# FTDI.net
KiCad netlist of a schematic drawn in Altium Designer
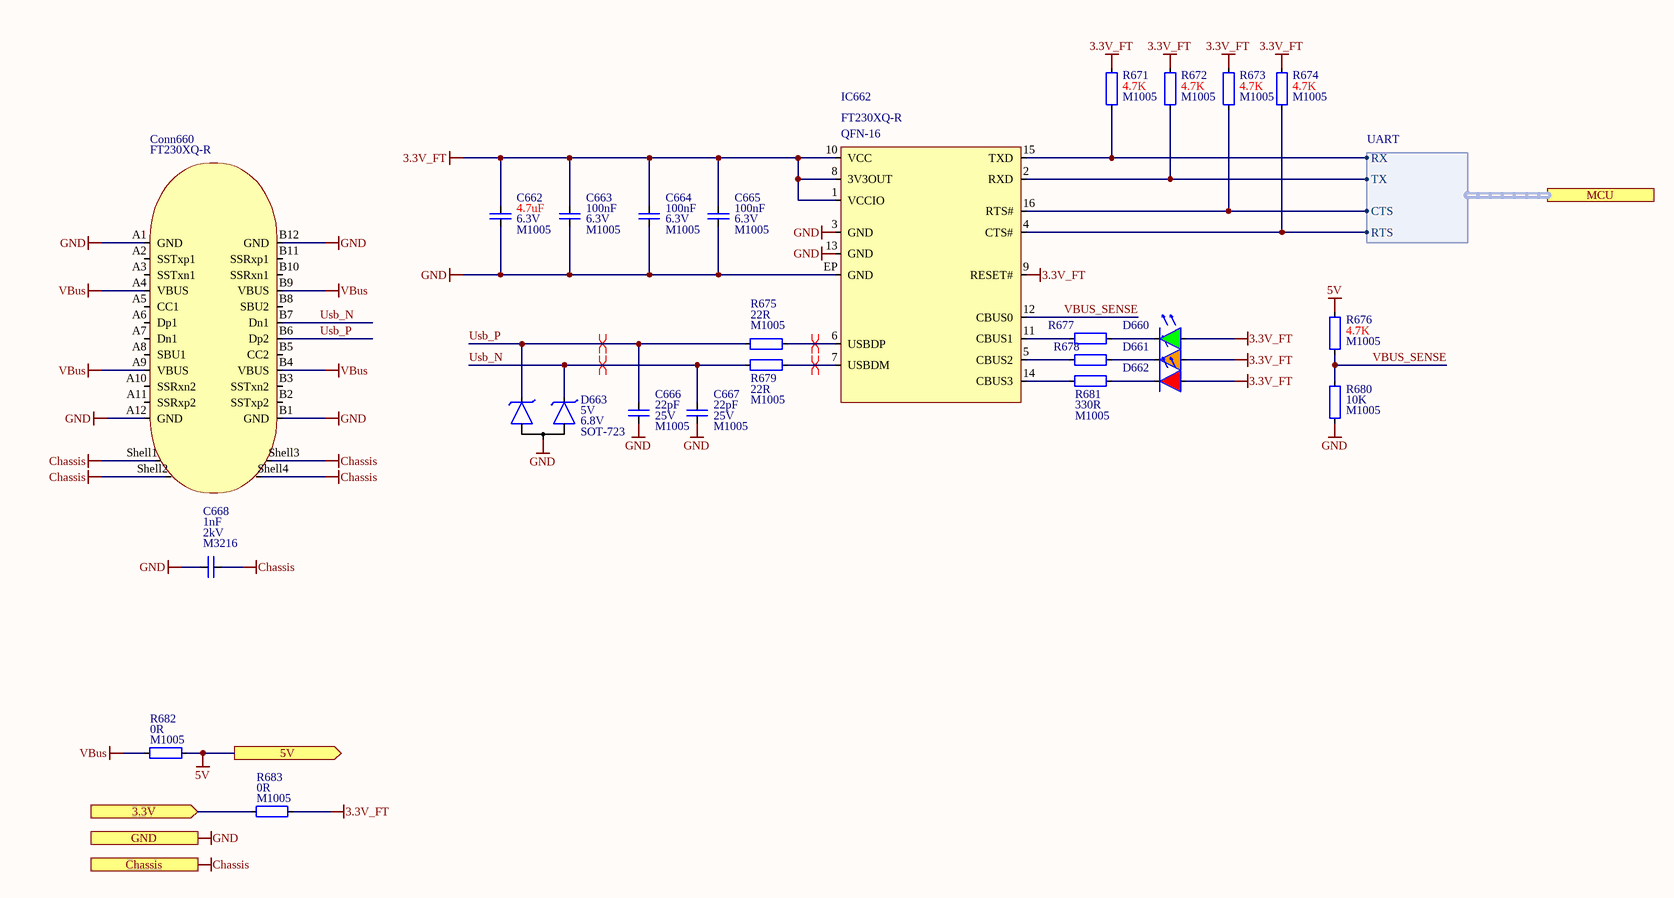
[diagram p0: FTDI.SchDoc]

(export (version "E")
  (design (tool "Eeschema 10.0.6"))
  (components
    (comp (ref "C662")
      (value "4.7uF")
      (footprint "Capacitor_Ceramic_M1005_I0402")
      (description "Cap, Cer, 100nF, 6.3V, M1005")
      (fields
        (field (name "VOLTAGE") "6.3V")
        (field (name "MANUFACTURER PART NUMBER") "04026D104KAT4A")
        (field (name "MANUFACTURER") "Kyocera")
        (field (name "PACKAGE") "M1005")
      )
      (libsource (lib "Capacitor") (part "Capacitor_Ceramic"))
    )
    (comp (ref "C663")
      (value "100nF")
      (footprint "Capacitor_Ceramic_M1005_I0402")
      (description "Cap, Cer, 100nF, 6.3V, M1005")
      (fields
        (field (name "VOLTAGE") "6.3V")
        (field (name "MANUFACTURER PART NUMBER") "04026D104KAT4A")
        (field (name "MANUFACTURER") "Kyocera")
        (field (name "PACKAGE") "M1005")
      )
      (libsource (lib "Capacitor") (part "Capacitor_Ceramic"))
    )
    (comp (ref "C664")
      (value "100nF")
      (footprint "Capacitor_Ceramic_M1005_I0402")
      (description "Cap, Cer, 100nF, 6.3V, M1005")
      (fields
        (field (name "VOLTAGE") "6.3V")
        (field (name "MANUFACTURER PART NUMBER") "04026D104KAT4A")
        (field (name "MANUFACTURER") "Kyocera")
        (field (name "PACKAGE") "M1005")
      )
      (libsource (lib "Capacitor") (part "Capacitor_Ceramic"))
    )
    (comp (ref "C665")
      (value "100nF")
      (footprint "Capacitor_Ceramic_M1005_I0402")
      (description "Cap, Cer, 100nF, 6.3V, M1005")
      (fields
        (field (name "VOLTAGE") "6.3V")
        (field (name "MANUFACTURER PART NUMBER") "04026D104KAT4A")
        (field (name "MANUFACTURER") "Kyocera")
        (field (name "PACKAGE") "M1005")
      )
      (libsource (lib "Capacitor") (part "Capacitor_Ceramic"))
    )
    (comp (ref "C666")
      (value "22pF")
      (footprint "Capacitor_Ceramic_M1005_I0402")
      (description "Cap, Cer, 22pF, 25V, M1005")
      (fields
        (field (name "VOLTAGE") "25V")
        (field (name "MANUFACTURER PART NUMBER") "0402N220J250CT")
        (field (name "MANUFACTURER") "Walsin")
        (field (name "PACKAGE") "M1005")
      )
      (libsource (lib "Capacitor") (part "Capacitor_Ceramic"))
    )
    (comp (ref "C667")
      (value "22pF")
      (footprint "Capacitor_Ceramic_M1005_I0402")
      (description "Cap, Cer, 22pF, 25V, M1005")
      (fields
        (field (name "VOLTAGE") "25V")
        (field (name "MANUFACTURER PART NUMBER") "0402N220J250CT")
        (field (name "MANUFACTURER") "Walsin")
        (field (name "PACKAGE") "M1005")
      )
      (libsource (lib "Capacitor") (part "Capacitor_Ceramic"))
    )
    (comp (ref "C668")
      (value "1nF")
      (footprint "Capacitor_Ceramic_M3216_I1206")
      (description "Cap, Cer, 1nF, 2kV, M3216")
      (fields
        (field (name "VOLTAGE") "2kV")
        (field (name "MANUFACTURER PART NUMBER") "CC1206MKX7RDBB102")
        (field (name "MANUFACTURER") "Yageo")
        (field (name "PACKAGE") "M3216")
      )
      (libsource (lib "Capacitor") (part "Capacitor_Ceramic"))
    )
    (comp (ref "Conn660")
      (value "GCT, USB4056")
      (footprint "GCT, USB4056")
      (description "IC,Interface,FTDI,QFN16")
      (fields (field (name "MANUFACTURER") "FTDI") (field (name "MANUFACTURER PART NUMBER") "FT230XQ-R"))
      (libsource (lib "Connector - USB") (part "GCT, USB4056"))
    )
    (comp (ref "D660")
      (value "Diode_Led")
      (footprint "Diode_Smd_M1608_I0603_Green-Yellow")
      (description "Diode, Led, Green-Yellow, 2.2V, 20mA, M1608")
      (fields (field (name "MANUFACTURER PART NUMBER") "SML-D12M1WT86") (field (name "MANUFACTURER") "Rohm"))
      (libsource (lib "Diode") (part "Diode_Led"))
    )
    (comp (ref "D661")
      (value "Diode_Led")
      (footprint "Diode_Smd_M1608_I0603_Orange1")
      (description "Diode, Led, Orange, 2.2V, 20mA, M1608")
      (fields (field (name "MANUFACTURER PART NUMBER") "SML-D12D1WT86") (field (name "MANUFACTURER") "Rohm"))
      (libsource (lib "Diode") (part "Diode_Led"))
    )
    (comp (ref "D662")
      (value "Diode_Led")
      (footprint "Diode_Smd_M1608_I0603_Red")
      (description "Diode, Led, Red, 2.2V, 20mA, M1608")
      (fields (field (name "MANUFACTURER PART NUMBER") "SML-D12U1WT86") (field (name "MANUFACTURER") "Rohm"))
      (libsource (lib "Diode") (part "Diode_Led"))
    )
    (comp (ref "D663")
      (value "Diode_Tvs_2P_Common_Anode")
      (footprint "Diode_SOT-723_2P_Common_Anode_Type_1")
      (description "Diode, TVS, 5V/6.8V, SOD-723")
      (fields
        (field (name "MANUFACTURER PART NUMBER") "DF3A6.8LFV,L3F")
        (field (name "MANUFACTURER") "Toshiba")
        (field (name "VOLTAGE, BREAK DOWN") "6.8V")
        (field (name "VOLTAGE, STAND OFF") "5V")
        (field (name "PACKAGE") "SOT-723")
      )
      (libsource (lib "Diode") (part "Diode_Tvs_2P_Common_Anode"))
    )
    (comp (ref "IC662")
      (value "FTDI_FT230XQ")
      (footprint "QFN-16, 4mm x 4mm, 0.65mm")
      (description "IC,Interface,FTDI,QFN16")
      (fields
        (field (name "MANUFACTURER") "FTDI")
        (field (name "MANUFACTURER PART NUMBER") "FT230XQ-R")
        (field (name "PACKAGE") "QFN-16")
      )
      (libsource (lib "IC-Interface") (part "FTDI_FT230XQ"))
    )
    (comp (ref "R671")
      (value "4.7K")
      (footprint "Resistor_Smd_M1005_I0402")
      (description "Res, 10K, 1%, M1005")
      (fields
        (field (name "TOLERANCE") "1%")
        (field (name "MANUFACTURER") "Yageo")
        (field (name "PACKAGE") "M1005")
      )
      (libsource (lib "Resistor") (part "Resistor"))
    )
    (comp (ref "R672")
      (value "4.7K")
      (footprint "Resistor_Smd_M1005_I0402")
      (description "Res, 10K, 1%, M1005")
      (fields
        (field (name "TOLERANCE") "1%")
        (field (name "MANUFACTURER") "Yageo")
        (field (name "PACKAGE") "M1005")
      )
      (libsource (lib "Resistor") (part "Resistor"))
    )
    (comp (ref "R673")
      (value "4.7K")
      (footprint "Resistor_Smd_M1005_I0402")
      (description "Res, 10K, 1%, M1005")
      (fields
        (field (name "TOLERANCE") "1%")
        (field (name "MANUFACTURER") "Yageo")
        (field (name "PACKAGE") "M1005")
      )
      (libsource (lib "Resistor") (part "Resistor"))
    )
    (comp (ref "R674")
      (value "4.7K")
      (footprint "Resistor_Smd_M1005_I0402")
      (description "Res, 10K, 1%, M1005")
      (fields
        (field (name "TOLERANCE") "1%")
        (field (name "MANUFACTURER") "Yageo")
        (field (name "PACKAGE") "M1005")
      )
      (libsource (lib "Resistor") (part "Resistor"))
    )
    (comp (ref "R675")
      (value "22R")
      (footprint "Resistor_Smd_M1005_I0402")
      (description "Res, 22R, 1%, M1005")
      (fields
        (field (name "TOLERANCE") "1%")
        (field (name "MANUFACTURER") "Yageo")
        (field (name "PACKAGE") "M1005")
      )
      (libsource (lib "Resistor") (part "Resistor"))
    )
    (comp (ref "R676")
      (value "4.7K")
      (footprint "Resistor_Smd_M1005_I0402")
      (description "Res, 10K, 1%, M1005")
      (fields
        (field (name "TOLERANCE") "1%")
        (field (name "MANUFACTURER") "Yageo")
        (field (name "PACKAGE") "M1005")
      )
      (libsource (lib "Resistor") (part "Resistor"))
    )
    (comp (ref "R677")
      (value "Resistor")
      (footprint "Resistor_Smd_M1005_I0402")
      (description "Res, 330R, 1%, M1005")
      (fields (field (name "TOLERANCE") "1%") (field (name "MANUFACTURER") "Yageo"))
      (libsource (lib "Resistor") (part "Resistor"))
    )
    (comp (ref "R678")
      (value "Resistor")
      (footprint "Resistor_Smd_M1005_I0402")
      (description "Res, 330R, 1%, M1005")
      (fields (field (name "TOLERANCE") "1%") (field (name "MANUFACTURER") "Yageo"))
      (libsource (lib "Resistor") (part "Resistor"))
    )
    (comp (ref "R679")
      (value "22R")
      (footprint "Resistor_Smd_M1005_I0402")
      (description "Res, 22R, 1%, M1005")
      (fields
        (field (name "TOLERANCE") "1%")
        (field (name "MANUFACTURER") "Yageo")
        (field (name "PACKAGE") "M1005")
      )
      (libsource (lib "Resistor") (part "Resistor"))
    )
    (comp (ref "R680")
      (value "10K")
      (footprint "Resistor_Smd_M1005_I0402")
      (description "Res, 10K, 1%, M1005")
      (fields
        (field (name "TOLERANCE") "1%")
        (field (name "MANUFACTURER") "Yageo")
        (field (name "PACKAGE") "M1005")
      )
      (libsource (lib "Resistor") (part "Resistor"))
    )
    (comp (ref "R681")
      (value "330R")
      (footprint "Resistor_Smd_M1005_I0402")
      (description "Res, 330R, 1%, M1005")
      (fields
        (field (name "TOLERANCE") "1%")
        (field (name "MANUFACTURER") "Yageo")
        (field (name "PACKAGE") "M1005")
      )
      (libsource (lib "Resistor") (part "Resistor"))
    )
    (comp (ref "R682")
      (value "0R")
      (footprint "Resistor_Smd_M1005_I0402")
      (description "Res, 0R, M1005")
      (fields
        (field (name "MANUFACTURER") "Yageo")
        (field (name "MANUFACTURER PART NUMBER") "RC0402FR-070RL")
        (field (name "PACKAGE") "M1005")
      )
      (libsource (lib "Resistor") (part "Resistor"))
    )
    (comp (ref "R683")
      (value "0R")
      (footprint "Resistor_Smd_M1005_I0402")
      (description "Res, 0R, M1005")
      (fields
        (field (name "MANUFACTURER") "Yageo")
        (field (name "MANUFACTURER PART NUMBER") "RC0402FR-070RL")
        (field (name "PACKAGE") "M1005")
      )
      (libsource (lib "Resistor") (part "Resistor"))
    )
  )
  (nets
    (net (code "2") (name "/3.3V") (class "Default")
      (node (ref "R683") (pin "1") (pinfunction "1_1") (pintype "passive"))
    )
    (net (code "3") (name "/Usb_N") (class "Default")
      (node (ref "C667") (pin "1") (pinfunction "1_1") (pintype "passive"))
      (node (ref "Conn660") (pin "B7") (pinfunction "Dn1_B7") (pintype "passive"))
      (node (ref "D663") (pin "C2") (pinfunction "C2_C2") (pintype "passive"))
      (node (ref "R679") (pin "1") (pinfunction "1_1") (pintype "passive"))
    )
    (net (code "4") (name "/Usb_P") (class "Default")
      (node (ref "C666") (pin "1") (pinfunction "1_1") (pintype "passive"))
      (node (ref "Conn660") (pin "B6") (pinfunction "Dp2_B6") (pintype "passive"))
      (node (ref "D663") (pin "C1") (pinfunction "C1_C1") (pintype "passive"))
      (node (ref "R675") (pin "1") (pinfunction "1_1") (pintype "passive"))
    )
    (net (code "5") (name "/VBUS_SENSE") (class "Default")
      (node (ref "IC662") (pin "12") (pinfunction "CBUS0_12") (pintype "passive"))
      (node (ref "R676") (pin "2") (pinfunction "2_2") (pintype "passive"))
      (node (ref "R680") (pin "1") (pinfunction "1_1") (pintype "passive"))
    )
    (net (code "7") (name "3.3V_FT") (class "Default")
      (node (ref "C662") (pin "1") (pinfunction "1_1") (pintype "passive"))
      (node (ref "C663") (pin "1") (pinfunction "1_1") (pintype "passive"))
      (node (ref "C664") (pin "1") (pinfunction "1_1") (pintype "passive"))
      (node (ref "C665") (pin "1") (pinfunction "1_1") (pintype "passive"))
      (node (ref "D660") (pin "A") (pinfunction "A_A") (pintype "passive"))
      (node (ref "D661") (pin "A") (pinfunction "A_A") (pintype "passive"))
      (node (ref "D662") (pin "A") (pinfunction "A_A") (pintype "passive"))
      (node (ref "IC662") (pin "1") (pinfunction "VCCIO_1") (pintype "passive"))
      (node (ref "IC662") (pin "10") (pinfunction "VCC_10") (pintype "passive"))
      (node (ref "IC662") (pin "8") (pinfunction "3V3OUT_8") (pintype "passive"))
      (node (ref "IC662") (pin "9") (pinfunction "RESET#_9") (pintype "passive"))
      (node (ref "R671") (pin "1") (pinfunction "1_1") (pintype "passive"))
      (node (ref "R672") (pin "1") (pinfunction "1_1") (pintype "passive"))
      (node (ref "R673") (pin "1") (pinfunction "1_1") (pintype "passive"))
      (node (ref "R674") (pin "1") (pinfunction "1_1") (pintype "passive"))
      (node (ref "R683") (pin "2") (pinfunction "2_2") (pintype "passive"))
    )
    (net (code "8") (name "5V") (class "Default")
      (node (ref "R676") (pin "1") (pinfunction "1_1") (pintype "passive"))
      (node (ref "R682") (pin "2") (pinfunction "2_2") (pintype "passive"))
    )
    (net (code "9") (name "Chassis") (class "Default")
      (node (ref "C668") (pin "2") (pinfunction "2_2") (pintype "passive"))
      (node (ref "Conn660") (pin "Shell1") (pinfunction "Chassis1_Shell1") (pintype "passive"))
      (node (ref "Conn660") (pin "Shell2") (pinfunction "Chassis2_Shell2") (pintype "passive"))
      (node (ref "Conn660") (pin "Shell3") (pinfunction "Chassis3_Shell3") (pintype "passive"))
      (node (ref "Conn660") (pin "Shell4") (pinfunction "Chassis4_Shell4") (pintype "passive"))
    )
    (net (code "10") (name "GND") (class "Default")
      (node (ref "C662") (pin "2") (pinfunction "2_2") (pintype "passive"))
      (node (ref "C663") (pin "2") (pinfunction "2_2") (pintype "passive"))
      (node (ref "C664") (pin "2") (pinfunction "2_2") (pintype "passive"))
      (node (ref "C665") (pin "2") (pinfunction "2_2") (pintype "passive"))
      (node (ref "C666") (pin "2") (pinfunction "2_2") (pintype "passive"))
      (node (ref "C667") (pin "2") (pinfunction "2_2") (pintype "passive"))
      (node (ref "C668") (pin "1") (pinfunction "1_1") (pintype "passive"))
      (node (ref "Conn660") (pin "A1") (pinfunction "GND_A1") (pintype "passive"))
      (node (ref "Conn660") (pin "A12") (pinfunction "GND_A12") (pintype "passive"))
      (node (ref "Conn660") (pin "B1") (pinfunction "GND_B1") (pintype "passive"))
      (node (ref "Conn660") (pin "B12") (pinfunction "GND_B12") (pintype "passive"))
      (node (ref "D663") (pin "A") (pinfunction "A_A") (pintype "passive"))
      (node (ref "IC662") (pin "13") (pinfunction "GND_13") (pintype "passive"))
      (node (ref "IC662") (pin "3") (pinfunction "GND_3") (pintype "passive"))
      (node (ref "IC662") (pin "EP") (pinfunction "GND_EP") (pintype "passive"))
      (node (ref "R680") (pin "2") (pinfunction "2_2") (pintype "passive"))
    )
    (net (code "11") (name "Net-(D660-PadC)") (class "Default")
      (node (ref "D660") (pin "C") (pinfunction "C_C") (pintype "passive"))
      (node (ref "R677") (pin "2") (pinfunction "2_2") (pintype "passive"))
    )
    (net (code "12") (name "Net-(D661-PadC)") (class "Default")
      (node (ref "D661") (pin "C") (pinfunction "C_C") (pintype "passive"))
      (node (ref "R678") (pin "2") (pinfunction "2_2") (pintype "passive"))
    )
    (net (code "13") (name "Net-(D662-PadC)") (class "Default")
      (node (ref "D662") (pin "C") (pinfunction "C_C") (pintype "passive"))
      (node (ref "R681") (pin "2") (pinfunction "2_2") (pintype "passive"))
    )
    (net (code "14") (name "Net-(IC662-CBUS1)") (class "Default")
      (node (ref "IC662") (pin "11") (pinfunction "CBUS1_11") (pintype "passive"))
      (node (ref "R677") (pin "1") (pinfunction "1_1") (pintype "passive"))
    )
    (net (code "15") (name "Net-(IC662-CBUS2)") (class "Default")
      (node (ref "IC662") (pin "5") (pinfunction "CBUS2_5") (pintype "passive"))
      (node (ref "R678") (pin "1") (pinfunction "1_1") (pintype "passive"))
    )
    (net (code "16") (name "Net-(IC662-CBUS3)") (class "Default")
      (node (ref "IC662") (pin "14") (pinfunction "CBUS3_14") (pintype "passive"))
      (node (ref "R681") (pin "1") (pinfunction "1_1") (pintype "passive"))
    )
    (net (code "17") (name "Net-(IC662-CTS#)") (class "Default")
      (node (ref "IC662") (pin "4") (pinfunction "CTS#_4") (pintype "passive"))
      (node (ref "R674") (pin "2") (pinfunction "2_2") (pintype "passive"))
    )
    (net (code "18") (name "Net-(IC662-RTS#)") (class "Default")
      (node (ref "IC662") (pin "16") (pinfunction "RTS#_16") (pintype "passive"))
      (node (ref "R673") (pin "2") (pinfunction "2_2") (pintype "passive"))
    )
    (net (code "19") (name "Net-(IC662-RXD)") (class "Default")
      (node (ref "IC662") (pin "2") (pinfunction "RXD_2") (pintype "passive"))
      (node (ref "R672") (pin "2") (pinfunction "2_2") (pintype "passive"))
    )
    (net (code "20") (name "Net-(IC662-TXD)") (class "Default")
      (node (ref "IC662") (pin "15") (pinfunction "TXD_15") (pintype "passive"))
      (node (ref "R671") (pin "2") (pinfunction "2_2") (pintype "passive"))
    )
    (net (code "21") (name "Net-(IC662-USBDM)") (class "Default")
      (node (ref "IC662") (pin "7") (pinfunction "USBDM_7") (pintype "passive"))
      (node (ref "R679") (pin "2") (pinfunction "2_2") (pintype "passive"))
    )
    (net (code "22") (name "Net-(IC662-USBDP)") (class "Default")
      (node (ref "IC662") (pin "6") (pinfunction "USBDP_6") (pintype "passive"))
      (node (ref "R675") (pin "2") (pinfunction "2_2") (pintype "passive"))
    )
    (net (code "23") (name "VBus") (class "Default")
      (node (ref "Conn660") (pin "A4") (pinfunction "VBUS_A4") (pintype "passive"))
      (node (ref "Conn660") (pin "A9") (pinfunction "VBUS_A9") (pintype "passive"))
      (node (ref "Conn660") (pin "B4") (pinfunction "VBUS_B4") (pintype "passive"))
      (node (ref "Conn660") (pin "B9") (pinfunction "VBUS_B9") (pintype "passive"))
      (node (ref "R682") (pin "1") (pinfunction "1_1") (pintype "passive"))
    )
    (net (code "24") (name "unconnected-(Conn660-CC1-PadA5)") (class "Default")
      (node (ref "Conn660") (pin "A5") (pinfunction "CC1_A5") (pintype "passive"))
    )
    (net (code "25") (name "unconnected-(Conn660-CC2-PadB5)") (class "Default")
      (node (ref "Conn660") (pin "B5") (pinfunction "CC2_B5") (pintype "passive"))
    )
    (net (code "26") (name "unconnected-(Conn660-Dn1-PadA7)") (class "Default")
      (node (ref "Conn660") (pin "A7") (pinfunction "Dn1_A7") (pintype "passive"))
    )
    (net (code "27") (name "unconnected-(Conn660-Dp1-PadA6)") (class "Default")
      (node (ref "Conn660") (pin "A6") (pinfunction "Dp1_A6") (pintype "passive"))
    )
    (net (code "28") (name "unconnected-(Conn660-SBU1-PadA8)") (class "Default")
      (node (ref "Conn660") (pin "A8") (pinfunction "SBU1_A8") (pintype "passive"))
    )
    (net (code "29") (name "unconnected-(Conn660-SBU2-PadB8)") (class "Default")
      (node (ref "Conn660") (pin "B8") (pinfunction "SBU2_B8") (pintype "passive"))
    )
    (net (code "30") (name "unconnected-(Conn660-SSRxn1-PadB10)") (class "Default")
      (node (ref "Conn660") (pin "B10") (pinfunction "SSRxn1_B10") (pintype "passive"))
    )
    (net (code "31") (name "unconnected-(Conn660-SSRxn2-PadA10)") (class "Default")
      (node (ref "Conn660") (pin "A10") (pinfunction "SSRxn2_A10") (pintype "passive"))
    )
    (net (code "32") (name "unconnected-(Conn660-SSRxp1-PadB11)") (class "Default")
      (node (ref "Conn660") (pin "B11") (pinfunction "SSRxp1_B11") (pintype "passive"))
    )
    (net (code "33") (name "unconnected-(Conn660-SSRxp2-PadA11)") (class "Default")
      (node (ref "Conn660") (pin "A11") (pinfunction "SSRxp2_A11") (pintype "passive"))
    )
    (net (code "34") (name "unconnected-(Conn660-SSTxn1-PadA3)") (class "Default")
      (node (ref "Conn660") (pin "A3") (pinfunction "SSTxn1_A3") (pintype "passive"))
    )
    (net (code "35") (name "unconnected-(Conn660-SSTxn2-PadB3)") (class "Default")
      (node (ref "Conn660") (pin "B3") (pinfunction "SSTxn2_B3") (pintype "passive"))
    )
    (net (code "36") (name "unconnected-(Conn660-SSTxp1-PadA2)") (class "Default")
      (node (ref "Conn660") (pin "A2") (pinfunction "SSTxp1_A2") (pintype "passive"))
    )
    (net (code "37") (name "unconnected-(Conn660-SSTxp2-PadB2)") (class "Default")
      (node (ref "Conn660") (pin "B2") (pinfunction "SSTxp2_B2") (pintype "passive"))
    )
  )
)
